# LEDproject_11_7_18.net
KiCad netlist of a schematic drawn in EAGLE
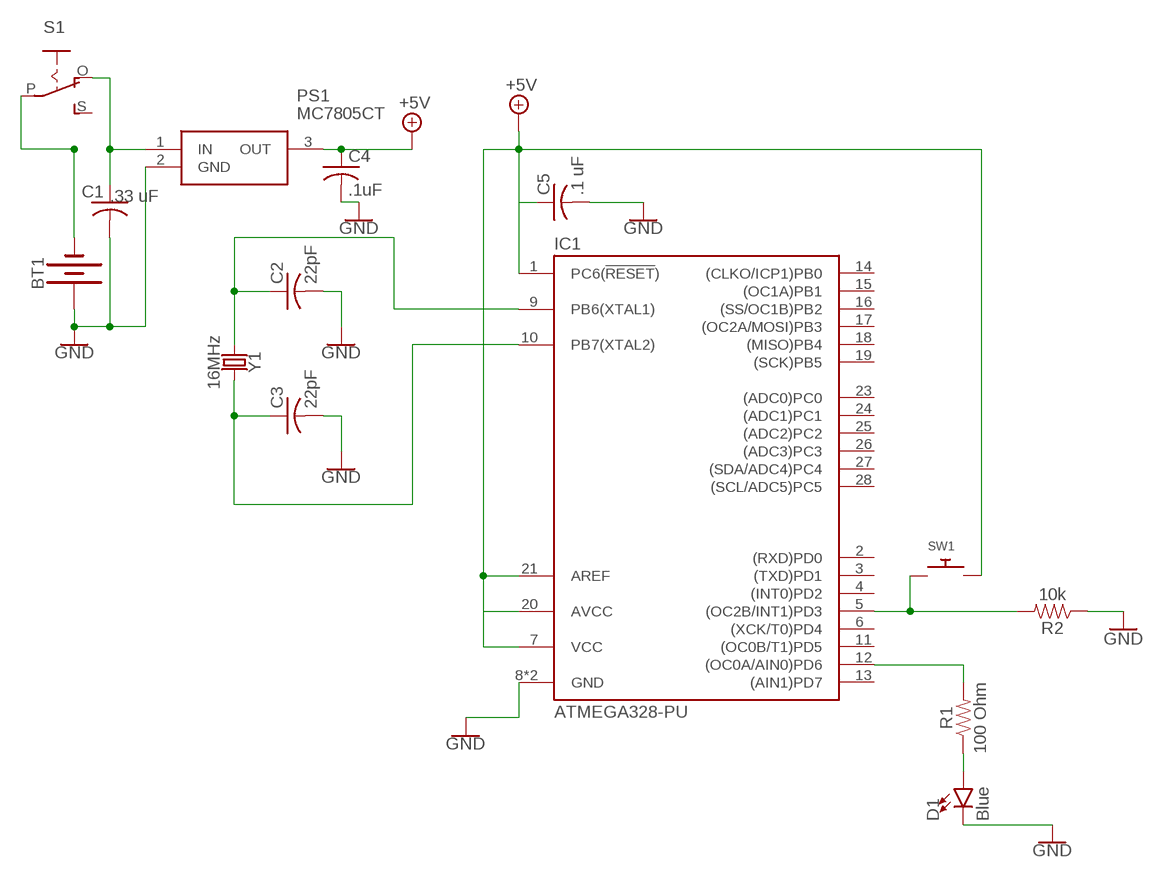
[diagram p0: schematic, sheet 1]

(export (version "E")
  (design (tool "Eeschema 10.0.6"))
  (components
    (comp (ref "BT1")
      (value "BATTERY-9V")
      (footprint "eagle-import:BATTCON_9V")
      (libsource (lib "eagle-import") (part "BATTERY-9V"))
    )
    (comp (ref "C1")
      (value "C-US025-030X050")
      (footprint "eagle-import:C025-030X050")
      (fields (field (name "BYPASS1") ".33 uF"))
      (libsource (lib "eagle-import") (part "C-US025-030X050"))
    )
    (comp (ref "C2")
      (value "22pF")
      (footprint "eagle-import:C025-030X050")
      (libsource (lib "eagle-import") (part "C-US025-030X050"))
    )
    (comp (ref "C3")
      (value "22pF")
      (footprint "eagle-import:C025-030X050")
      (libsource (lib "eagle-import") (part "C-US025-030X050"))
    )
    (comp (ref "C4")
      (value ".1uF")
      (footprint "eagle-import:C025-030X050")
      (libsource (lib "eagle-import") (part "C-US025-030X050"))
    )
    (comp (ref "C5")
      (value ".1 uF")
      (footprint "eagle-import:C025-030X050")
      (libsource (lib "eagle-import") (part "C-US025-030X050"))
    )
    (comp (ref "D1")
      (value "Blue")
      (footprint "eagle-import:LED_5MM")
      (libsource (lib "eagle-import") (part "LED5MM"))
    )
    (comp (ref "IC1")
      (value "ATMEGA328-PU")
      (footprint "eagle-import:DIL28")
      (fields (field (name "DIGI-KEY_PART_NUMBER") "ATMEGA328-PU-ND") (field (name "MF") "Microchip"))
      (libsource (lib "eagle-import") (part "ATMEGA328-PU"))
    )
    (comp (ref "PS1")
      (value "MC7805CT")
      (footprint "eagle-import:TO254P482X997X1968-3P")
      (fields (field (name "MOUSER_PART_NUMBER") "863-MC7805CT"))
      (libsource (lib "eagle-import") (part "MC7805CT"))
    )
    (comp (ref "R1")
      (value "100 Ohm")
      (footprint "eagle-import:0603")
      (libsource (lib "eagle-import") (part "150OHM-0603-1/10W-1%"))
    )
    (comp (ref "R2")
      (value "10k")
      (footprint "eagle-import:AXIAL-0.3")
      (libsource (lib "eagle-import") (part "10KOHM-HORIZ-1/4W-1%"))
    )
    (comp (ref "S1")
      (value "EG1218S")
      (footprint "eagle-import:EG1218")
      (libsource (lib "eagle-import") (part "EG1218S"))
    )
    (comp (ref "SW1")
      (value "SWITCH_PUSHBUTTONEVQ-PE")
      (footprint "eagle-import:TACT_PANA-EVQ")
      (libsource (lib "eagle-import") (part "SWITCH_PUSHBUTTONEVQ-PE"))
    )
    (comp (ref "Y1")
      (value "16MHz")
      (footprint "eagle-import:HC49US")
      (libsource (lib "eagle-import") (part "CRYSTAL-16MHZPTH-HC49US"))
    )
  )
  (nets
    (net (code "1") (name "+5V") (class "Default")
      (node (ref "C4") (pin "1") (pinfunction "1_1") (pintype "passive"))
      (node (ref "C5") (pin "1") (pinfunction "1_1") (pintype "passive"))
      (node (ref "IC1") (pin "1") (pinfunction "PC6(~{RESET})_1") (pintype "bidirectional"))
      (node (ref "IC1") (pin "20") (pinfunction "AVCC_20") (pintype "power_in"))
      (node (ref "IC1") (pin "21") (pinfunction "AREF_21") (pintype "passive"))
      (node (ref "IC1") (pin "7") (pinfunction "VCC_7") (pintype "power_in"))
      (node (ref "PS1") (pin "3") (pinfunction "OUT_3") (pintype "output"))
      (node (ref "SW1") (pin "P$2") (pinfunction "P$2_P$2") (pintype "passive"))
    )
    (net (code "2") (name "GND") (class "Default")
      (node (ref "BT1") (pin "+") (pinfunction "+_+") (pintype "power_in"))
      (node (ref "C1") (pin "2") (pinfunction "2_2") (pintype "passive"))
      (node (ref "C2") (pin "2") (pinfunction "2_2") (pintype "passive"))
      (node (ref "C3") (pin "2") (pinfunction "2_2") (pintype "passive"))
      (node (ref "C4") (pin "2") (pinfunction "2_2") (pintype "passive"))
      (node (ref "C5") (pin "2") (pinfunction "2_2") (pintype "passive"))
      (node (ref "D1") (pin "K") (pinfunction "C_K") (pintype "passive"))
      (node (ref "IC1") (pin "22") (pinfunction "GND_22") (pintype "power_in"))
      (node (ref "IC1") (pin "8") (pinfunction "GND_8") (pintype "power_in"))
      (node (ref "PS1") (pin "2") (pinfunction "GND_2") (pintype "power_in"))
      (node (ref "R2") (pin "P$1") (pinfunction "1_P$1") (pintype "passive"))
    )
    (net (code "3") (name "Net-(BT1-Pad-)") (class "Default")
      (node (ref "BT1") (pin "-") (pinfunction "-_-") (pintype "power_in"))
      (node (ref "S1") (pin "P") (pinfunction "P_P") (pintype "passive"))
    )
    (net (code "4") (name "Net-(D1-PadA)") (class "Default")
      (node (ref "D1") (pin "A") (pinfunction "A_A") (pintype "passive"))
      (node (ref "R1") (pin "1") (pinfunction "1_1") (pintype "passive"))
    )
    (net (code "5") (name "Net-(IC1-(OC0A{slash}AIN0)PD6)") (class "Default")
      (node (ref "IC1") (pin "12") (pinfunction "(OC0A/AIN0)PD6_12") (pintype "bidirectional"))
      (node (ref "R1") (pin "2") (pinfunction "2_2") (pintype "passive"))
    )
    (net (code "6") (name "Net-(IC1-(OC2B{slash}INT1)PD3)") (class "Default")
      (node (ref "IC1") (pin "5") (pinfunction "(OC2B/INT1)PD3_5") (pintype "bidirectional"))
      (node (ref "R2") (pin "P$2") (pinfunction "2_P$2") (pintype "passive"))
      (node (ref "SW1") (pin "P$1") (pinfunction "P$1_P$1") (pintype "passive"))
    )
    (net (code "7") (name "Net-(IC1-PB6(XTAL1))") (class "Default")
      (node (ref "C2") (pin "1") (pinfunction "1_1") (pintype "passive"))
      (node (ref "IC1") (pin "9") (pinfunction "PB6(XTAL1)_9") (pintype "bidirectional"))
      (node (ref "Y1") (pin "1") (pinfunction "1_1") (pintype "passive"))
    )
    (net (code "8") (name "Net-(IC1-PB7(XTAL2))") (class "Default")
      (node (ref "C3") (pin "1") (pinfunction "1_1") (pintype "passive"))
      (node (ref "IC1") (pin "10") (pinfunction "PB7(XTAL2)_10") (pintype "bidirectional"))
      (node (ref "Y1") (pin "2") (pinfunction "2_2") (pintype "passive"))
    )
    (net (code "9") (name "Net-(PS1-IN)") (class "Default")
      (node (ref "C1") (pin "1") (pinfunction "1_1") (pintype "passive"))
      (node (ref "PS1") (pin "1") (pinfunction "IN_1") (pintype "input"))
      (node (ref "S1") (pin "O") (pinfunction "O_O") (pintype "passive"))
    )
    (net (code "10") (name "unconnected-(IC1-(ADC0)PC0-Pad23)") (class "Default")
      (node (ref "IC1") (pin "23") (pinfunction "(ADC0)PC0_23") (pintype "bidirectional"))
    )
    (net (code "11") (name "unconnected-(IC1-(ADC1)PC1-Pad24)") (class "Default")
      (node (ref "IC1") (pin "24") (pinfunction "(ADC1)PC1_24") (pintype "bidirectional"))
    )
    (net (code "12") (name "unconnected-(IC1-(ADC2)PC2-Pad25)") (class "Default")
      (node (ref "IC1") (pin "25") (pinfunction "(ADC2)PC2_25") (pintype "bidirectional"))
    )
    (net (code "13") (name "unconnected-(IC1-(ADC3)PC3-Pad26)") (class "Default")
      (node (ref "IC1") (pin "26") (pinfunction "(ADC3)PC3_26") (pintype "bidirectional"))
    )
    (net (code "14") (name "unconnected-(IC1-(AIN1)PD7-Pad13)") (class "Default")
      (node (ref "IC1") (pin "13") (pinfunction "(AIN1)PD7_13") (pintype "bidirectional"))
    )
    (net (code "15") (name "unconnected-(IC1-(CLKO{slash}ICP1)PB0-Pad14)") (class "Default")
      (node (ref "IC1") (pin "14") (pinfunction "(CLKO/ICP1)PB0_14") (pintype "bidirectional"))
    )
    (net (code "16") (name "unconnected-(IC1-(INT0)PD2-Pad4)") (class "Default")
      (node (ref "IC1") (pin "4") (pinfunction "(INT0)PD2_4") (pintype "bidirectional"))
    )
    (net (code "17") (name "unconnected-(IC1-(MISO)PB4-Pad18)") (class "Default")
      (node (ref "IC1") (pin "18") (pinfunction "(MISO)PB4_18") (pintype "bidirectional"))
    )
    (net (code "18") (name "unconnected-(IC1-(OC0B{slash}T1)PD5-Pad11)") (class "Default")
      (node (ref "IC1") (pin "11") (pinfunction "(OC0B/T1)PD5_11") (pintype "bidirectional"))
    )
    (net (code "19") (name "unconnected-(IC1-(OC1A)PB1-Pad15)") (class "Default")
      (node (ref "IC1") (pin "15") (pinfunction "(OC1A)PB1_15") (pintype "bidirectional"))
    )
    (net (code "20") (name "unconnected-(IC1-(OC2A{slash}MOSI)PB3-Pad17)") (class "Default")
      (node (ref "IC1") (pin "17") (pinfunction "(OC2A/MOSI)PB3_17") (pintype "bidirectional"))
    )
    (net (code "21") (name "unconnected-(IC1-(RXD)PD0-Pad2)") (class "Default")
      (node (ref "IC1") (pin "2") (pinfunction "(RXD)PD0_2") (pintype "bidirectional"))
    )
    (net (code "22") (name "unconnected-(IC1-(SCK)PB5-Pad19)") (class "Default")
      (node (ref "IC1") (pin "19") (pinfunction "(SCK)PB5_19") (pintype "bidirectional"))
    )
    (net (code "23") (name "unconnected-(IC1-(SCL{slash}ADC5)PC5-Pad28)") (class "Default")
      (node (ref "IC1") (pin "28") (pinfunction "(SCL/ADC5)PC5_28") (pintype "bidirectional"))
    )
    (net (code "24") (name "unconnected-(IC1-(SDA{slash}ADC4)PC4-Pad27)") (class "Default")
      (node (ref "IC1") (pin "27") (pinfunction "(SDA/ADC4)PC4_27") (pintype "bidirectional"))
    )
    (net (code "25") (name "unconnected-(IC1-(SS{slash}OC1B)PB2-Pad16)") (class "Default")
      (node (ref "IC1") (pin "16") (pinfunction "(SS/OC1B)PB2_16") (pintype "bidirectional"))
    )
    (net (code "26") (name "unconnected-(IC1-(TXD)PD1-Pad3)") (class "Default")
      (node (ref "IC1") (pin "3") (pinfunction "(TXD)PD1_3") (pintype "bidirectional"))
    )
    (net (code "27") (name "unconnected-(IC1-(XCK{slash}T0)PD4-Pad6)") (class "Default")
      (node (ref "IC1") (pin "6") (pinfunction "(XCK/T0)PD4_6") (pintype "bidirectional"))
    )
    (net (code "28") (name "unconnected-(S1-PadS)") (class "Default")
      (node (ref "S1") (pin "S") (pinfunction "S_S") (pintype "passive"))
    )
  )
)
